# analog_supply_decoupling.net
KiCad netlist of a schematic drawn in Altium Designer
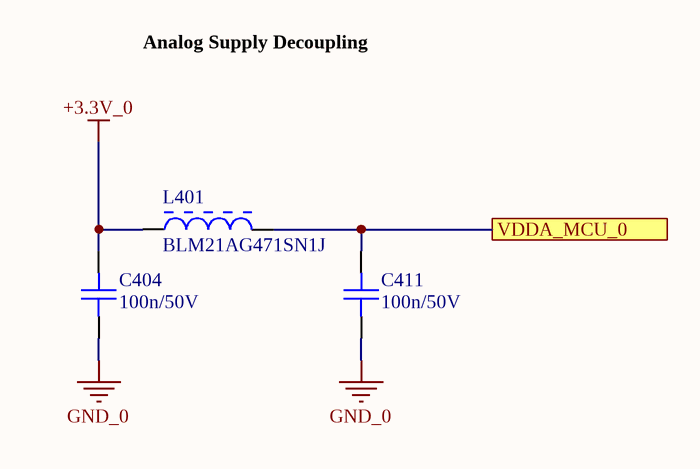
[diagram p0: analog_supply_decoupling.SchDoc]

(export (version "E")
  (design (tool "Eeschema 10.0.6"))
  (components
    (comp (ref "C404")
      (value "100n/50V")
      (footprint "CAPC1608X08N")
      (description "MLCC")
      (fields (field (name "PART NUMBER") "gen_C_ceramic_100n_50V_X7R_0603"))
      (libsource (lib "OE750") (part "C"))
    )
    (comp (ref "C411")
      (value "100n/50V")
      (footprint "CAPC1608X08N")
      (description "MLCC")
      (fields (field (name "PART NUMBER") "gen_C_ceramic_100n_50V_X7R_0603"))
      (libsource (lib "OE750") (part "C"))
    )
    (comp (ref "L401")
      (value "BLM21AG471SN1J")
      (footprint "MURA-BLM21-H1-CHIP-2_V")
      (fields (field (name "MANUFACTURER") "Murata"))
      (libsource (lib "Altium Content Vault") (part "MURA-FB-2"))
    )
  )
  (nets
    (net (code "1") (name "+3.3V_0") (class "Default")
      (node (ref "C404") (pin "1") (pinfunction "1_1") (pintype "passive"))
      (node (ref "L401") (pin "1") (pinfunction "1_1") (pintype "passive"))
    )
    (net (code "2") (name "/VDDA_MCU_0") (class "Default")
      (node (ref "C411") (pin "1") (pinfunction "1_1") (pintype "passive"))
      (node (ref "L401") (pin "2") (pinfunction "2_2") (pintype "passive"))
    )
    (net (code "3") (name "GND_0") (class "Default")
      (node (ref "C404") (pin "2") (pinfunction "2_2") (pintype "passive"))
      (node (ref "C411") (pin "2") (pinfunction "2_2") (pintype "passive"))
    )
  )
)
